# RoverBreakout2.net
KiCad netlist of a schematic drawn in Altium Designer
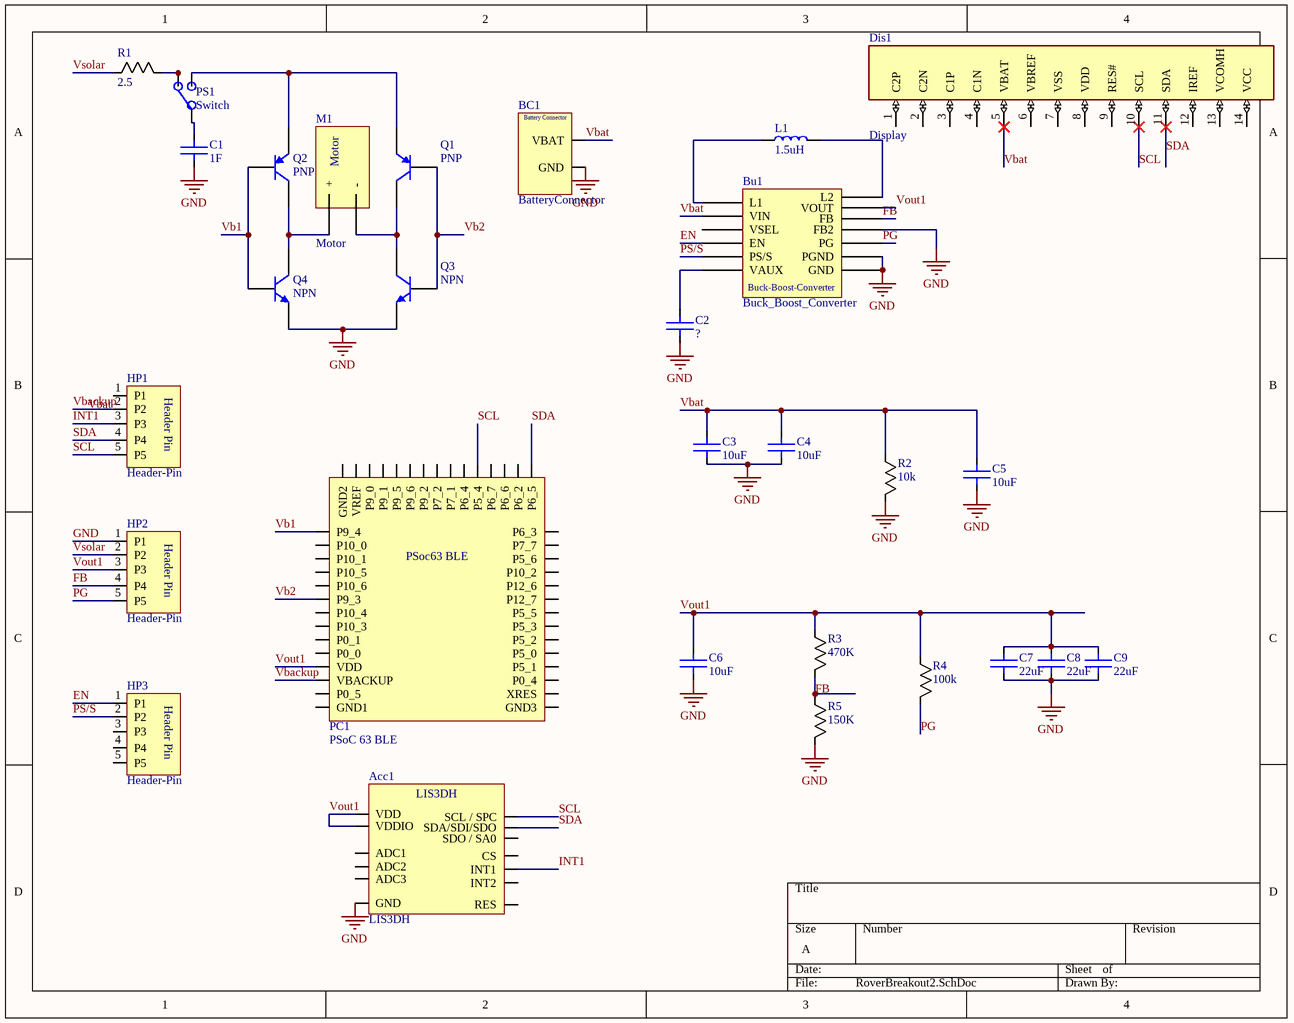
[diagram p0: RoverBreakout2.SchDoc]

(export (version "E")
  (design (tool "Eeschema 10.0.6"))
  (components
    (comp (ref "Acc1") (value "LIS3DH") (footprint "LIS3DH") (libsource (lib "SeniorDesign") (part "LIS3DH")))
    (comp (ref "BC1")
      (value "BatteryConnector")
      (footprint "BatteryConnector")
      (libsource (lib "SeniorDesign") (part "BatteryConnector"))
    )
    (comp (ref "Bu1")
      (value "Buck_Boost_Converter")
      (footprint "Buck_Boost_Converter")
      (libsource (lib "ISeniorDesign") (part "Buck_Boost_Converter"))
    )
    (comp (ref "C1")
      (value "1F")
      (footprint "PASSIVE-CAPACITOR-0603")
      (fields (field (name "Comment") "Capacitor1"))
      (libsource (lib "ISeniorDesign") (part "Capacitor1"))
    )
    (comp (ref "C2")
      (value "?")
      (footprint "PASSIVE-CAPACITOR-0603")
      (fields (field (name "Comment") "Capacitor1"))
      (libsource (lib "ISeniorDesign") (part "Capacitor1"))
    )
    (comp (ref "C3")
      (value "10uF")
      (footprint "PASSIVE-CAPACITOR-0603")
      (fields (field (name "Comment") "Capacitor1"))
      (libsource (lib "ISeniorDesign") (part "Capacitor1"))
    )
    (comp (ref "C4")
      (value "10uF")
      (footprint "PASSIVE-CAPACITOR-0603")
      (fields (field (name "Comment") "Capacitor1"))
      (libsource (lib "ISeniorDesign") (part "Capacitor1"))
    )
    (comp (ref "C5")
      (value "10uF")
      (footprint "PASSIVE-CAPACITOR-0603")
      (fields (field (name "Comment") "Capacitor1"))
      (libsource (lib "ISeniorDesign") (part "Capacitor1"))
    )
    (comp (ref "C6")
      (value "10uF")
      (footprint "PASSIVE-CAPACITOR-0603")
      (fields (field (name "Comment") "Capacitor1"))
      (libsource (lib "ISeniorDesign") (part "Capacitor1"))
    )
    (comp (ref "C7")
      (value "22uF")
      (footprint "PASSIVE-CAPACITOR-0603")
      (fields (field (name "Comment") "Capacitor1"))
      (libsource (lib "ISeniorDesign") (part "Capacitor1"))
    )
    (comp (ref "C8")
      (value "22uF")
      (footprint "PASSIVE-CAPACITOR-0603")
      (fields (field (name "Comment") "Capacitor1"))
      (libsource (lib "ISeniorDesign") (part "Capacitor1"))
    )
    (comp (ref "C9")
      (value "22uF")
      (footprint "PASSIVE-CAPACITOR-0603")
      (fields (field (name "Comment") "Capacitor1"))
      (libsource (lib "ISeniorDesign") (part "Capacitor1"))
    )
    (comp (ref "Dis1")
      (value "Display")
      (footprint "Display")
      (libsource (lib "SeniorDesign") (part "Display"))
    )
    (comp (ref "HP1")
      (value "Header-Pin")
      (footprint "Header_Pin")
      (libsource (lib "SeniorDesign") (part "Header-Pin"))
    )
    (comp (ref "HP2")
      (value "Header-Pin")
      (footprint "Header_Pin")
      (libsource (lib "SeniorDesign") (part "Header-Pin"))
    )
    (comp (ref "HP3")
      (value "Header-Pin")
      (footprint "Header_Pin")
      (libsource (lib "SeniorDesign") (part "Header-Pin"))
    )
    (comp (ref "L1")
      (value "1.5uH")
      (footprint "PASSIVE-INDUCTOR-0603")
      (fields (field (name "Comment") "Inductor"))
      (libsource (lib "ISeniorDesign") (part "Inductor"))
    )
    (comp (ref "M1") (value "Motor") (footprint "Motor") (libsource (lib "ISeniorDesign") (part "Motor")))
    (comp (ref "PC1")
      (value "PSoC 63 BLE")
      (footprint "PSoC-63 BLE")
      (libsource (lib "ISeniorDesign") (part "PSoC 63 BLE"))
    )
    (comp (ref "PS1")
      (value "Switch")
      (footprint "3-Way Switch")
      (libsource (lib "SeniorDesign") (part "Switch"))
    )
    (comp (ref "Q1")
      (value "PNP")
      (footprint "SOT-23B_N")
      (description "PNP Bipolar Transistor")
      (fields (field (name "PUBLISHER") "Altium Limited"))
      (libsource (lib "Miscellaneous Devices") (part "PNP"))
    )
    (comp (ref "Q2")
      (value "PNP")
      (footprint "SOT-23B_N")
      (description "PNP Bipolar Transistor")
      (fields (field (name "PUBLISHER") "Altium Limited"))
      (libsource (lib "Miscellaneous Devices") (part "PNP"))
    )
    (comp (ref "Q3")
      (value "NPN")
      (footprint "TO-226-AA")
      (description "NPN Bipolar Transistor")
      (fields (field (name "PUBLISHER") "Altium Limited"))
      (libsource (lib "Miscellaneous Devices") (part "NPN"))
    )
    (comp (ref "Q4")
      (value "NPN")
      (footprint "TO-226-AA")
      (description "NPN Bipolar Transistor")
      (fields (field (name "PUBLISHER") "Altium Limited"))
      (libsource (lib "Miscellaneous Devices") (part "NPN"))
    )
    (comp (ref "R1")
      (value "2.5")
      (footprint "PASSIVE-RESISTOR-0603")
      (fields (field (name "Comment") "Resistor"))
      (libsource (lib "ISeniorDesign") (part "Resistor1"))
    )
    (comp (ref "R2")
      (value "10k")
      (footprint "PASSIVE-RESISTOR-0603")
      (fields (field (name "Comment") "Resistor"))
      (libsource (lib "ISeniorDesign") (part "Resistor1"))
    )
    (comp (ref "R3")
      (value "470K")
      (footprint "PASSIVE-RESISTOR-0603")
      (fields (field (name "Comment") "Resistor"))
      (libsource (lib "ISeniorDesign") (part "Resistor1"))
    )
    (comp (ref "R4")
      (value "100k")
      (footprint "PASSIVE-RESISTOR-0603")
      (fields (field (name "Comment") "Resistor"))
      (libsource (lib "ISeniorDesign") (part "Resistor1"))
    )
    (comp (ref "R5")
      (value "150K")
      (footprint "PASSIVE-RESISTOR-0603")
      (fields (field (name "Comment") "Resistor"))
      (libsource (lib "ISeniorDesign") (part "Resistor1"))
    )
  )
  (nets
    (net (code "1") (name "/EN") (class "Default")
      (node (ref "Bu1") (pin "EN") (pinfunction "EN_EN") (pintype "passive"))
      (node (ref "HP3") (pin "1") (pinfunction "P1_1") (pintype "passive"))
    )
    (net (code "2") (name "/FB") (class "Default")
      (node (ref "Bu1") (pin "FB") (pinfunction "FB_FB") (pintype "passive"))
      (node (ref "HP2") (pin "4") (pinfunction "P4_4") (pintype "passive"))
      (node (ref "R3") (pin "2") (pinfunction "2_2") (pintype "passive"))
      (node (ref "R5") (pin "1") (pinfunction "1_1") (pintype "passive"))
    )
    (net (code "3") (name "/INT1") (class "Default")
      (node (ref "Acc1") (pin "INT1") (pinfunction "INT1_INT1") (pintype "passive"))
      (node (ref "HP1") (pin "3") (pinfunction "P3_3") (pintype "passive"))
    )
    (net (code "4") (name "/PG") (class "Default")
      (node (ref "Bu1") (pin "PG") (pinfunction "PG_PG") (pintype "passive"))
      (node (ref "HP2") (pin "5") (pinfunction "P5_5") (pintype "passive"))
      (node (ref "R4") (pin "2") (pinfunction "2_2") (pintype "passive"))
    )
    (net (code "5") (name "/PS{slash}S") (class "Default")
      (node (ref "Bu1") (pin "PS/S") (pinfunction "PS/S_PS/S") (pintype "passive"))
      (node (ref "HP3") (pin "2") (pinfunction "P2_2") (pintype "passive"))
    )
    (net (code "6") (name "/SCL") (class "Default")
      (node (ref "Acc1") (pin "SCL_/_SPC") (pinfunction "SCL_/_SPC_SCL_/_SPC") (pintype "passive"))
      (node (ref "Dis1") (pin "10") (pinfunction "SCL_10") (pintype "bidirectional"))
      (node (ref "HP1") (pin "5") (pinfunction "P5_5") (pintype "passive"))
      (node (ref "PC1") (pin "25") (pinfunction "P5_4_25") (pintype "passive"))
    )
    (net (code "7") (name "/SDA") (class "Default")
      (node (ref "Acc1") (pin "SDA/SDI/SDO") (pinfunction "SDA/SDI/SDO_SDA/SDI/SDO") (pintype "passive"))
      (node (ref "Dis1") (pin "11") (pinfunction "SDA_11") (pintype "bidirectional"))
      (node (ref "HP1") (pin "4") (pinfunction "P4_4") (pintype "passive"))
      (node (ref "PC1") (pin "29") (pinfunction "P6_5_29") (pintype "passive"))
    )
    (net (code "8") (name "/Vb1") (class "Default")
      (node (ref "PC1") (pin "14") (pinfunction "P9_4_14") (pintype "passive"))
      (node (ref "Q2") (pin "2") (pinfunction "B_2") (pintype "passive"))
      (node (ref "Q4") (pin "2") (pinfunction "B_2") (pintype "passive"))
    )
    (net (code "9") (name "/Vb2") (class "Default")
      (node (ref "PC1") (pin "9") (pinfunction "P9_3_9") (pintype "passive"))
      (node (ref "Q1") (pin "2") (pinfunction "B_2") (pintype "passive"))
      (node (ref "Q3") (pin "2") (pinfunction "B_2") (pintype "passive"))
    )
    (net (code "10") (name "/Vbackup") (class "Default")
      (node (ref "HP1") (pin "2") (pinfunction "P2_2") (pintype "passive"))
      (node (ref "PC1") (pin "3") (pinfunction "VBACKUP_3") (pintype "passive"))
    )
    (net (code "11") (name "/Vbat") (class "Default")
      (node (ref "BC1") (pin "VBAT") (pinfunction "VBAT_VBAT") (pintype "passive"))
      (node (ref "Bu1") (pin "VIN") (pinfunction "VIN_VIN") (pintype "passive"))
      (node (ref "C3") (pin "2") (pinfunction "2_2") (pintype "passive"))
      (node (ref "C4") (pin "2") (pinfunction "2_2") (pintype "passive"))
      (node (ref "C5") (pin "2") (pinfunction "2_2") (pintype "passive"))
      (node (ref "Dis1") (pin "5") (pinfunction "VBAT_5") (pintype "bidirectional"))
      (node (ref "HP1") (pin "1") (pinfunction "P1_1") (pintype "passive"))
      (node (ref "R2") (pin "1") (pinfunction "1_1") (pintype "passive"))
    )
    (net (code "12") (name "/Vout1") (class "Default")
      (node (ref "Acc1") (pin "VDD") (pinfunction "VDD_VDD") (pintype "passive"))
      (node (ref "Acc1") (pin "VDDIO") (pinfunction "VDDIO_VDDIO") (pintype "passive"))
      (node (ref "Bu1") (pin "VOUT") (pinfunction "VOUT_VOUT") (pintype "passive"))
      (node (ref "C6") (pin "2") (pinfunction "2_2") (pintype "passive"))
      (node (ref "C7") (pin "2") (pinfunction "2_2") (pintype "passive"))
      (node (ref "C8") (pin "2") (pinfunction "2_2") (pintype "passive"))
      (node (ref "C9") (pin "2") (pinfunction "2_2") (pintype "passive"))
      (node (ref "HP2") (pin "3") (pinfunction "P3_3") (pintype "passive"))
      (node (ref "PC1") (pin "4") (pinfunction "VDD_4") (pintype "passive"))
      (node (ref "R3") (pin "1") (pinfunction "1_1") (pintype "passive"))
      (node (ref "R4") (pin "1") (pinfunction "1_1") (pintype "passive"))
    )
    (net (code "13") (name "/Vsolar") (class "Default")
      (node (ref "HP2") (pin "2") (pinfunction "P2_2") (pintype "passive"))
      (node (ref "R1") (pin "1") (pinfunction "1_1") (pintype "passive"))
    )
    (net (code "14") (name "GND") (class "Default")
      (node (ref "Acc1") (pin "GND") (pinfunction "GND_GND") (pintype "passive"))
      (node (ref "BC1") (pin "GND") (pinfunction "GND_GND") (pintype "passive"))
      (node (ref "Bu1") (pin "FB2") (pinfunction "FB2_FB2") (pintype "passive"))
      (node (ref "Bu1") (pin "GND") (pinfunction "GND_GND") (pintype "passive"))
      (node (ref "Bu1") (pin "PGND") (pinfunction "PGND_PGND") (pintype "passive"))
      (node (ref "C1") (pin "1") (pinfunction "1_1") (pintype "passive"))
      (node (ref "C2") (pin "1") (pinfunction "1_1") (pintype "passive"))
      (node (ref "C3") (pin "1") (pinfunction "1_1") (pintype "passive"))
      (node (ref "C4") (pin "1") (pinfunction "1_1") (pintype "passive"))
      (node (ref "C5") (pin "1") (pinfunction "1_1") (pintype "passive"))
      (node (ref "C6") (pin "1") (pinfunction "1_1") (pintype "passive"))
      (node (ref "C7") (pin "1") (pinfunction "1_1") (pintype "passive"))
      (node (ref "C8") (pin "1") (pinfunction "1_1") (pintype "passive"))
      (node (ref "C9") (pin "1") (pinfunction "1_1") (pintype "passive"))
      (node (ref "HP2") (pin "1") (pinfunction "P1_1") (pintype "passive"))
      (node (ref "Q3") (pin "3") (pinfunction "E_3") (pintype "passive"))
      (node (ref "Q4") (pin "3") (pinfunction "E_3") (pintype "passive"))
      (node (ref "R2") (pin "2") (pinfunction "2_2") (pintype "passive"))
      (node (ref "R5") (pin "2") (pinfunction "2_2") (pintype "passive"))
    )
    (net (code "15") (name "Net-(Bu1-PadL1)") (class "Default")
      (node (ref "Bu1") (pin "L1") (pinfunction "L1_L1") (pintype "passive"))
      (node (ref "L1") (pin "1") (pinfunction "1_1") (pintype "passive"))
    )
    (net (code "16") (name "Net-(Bu1-PadL2)") (class "Default")
      (node (ref "Bu1") (pin "L2") (pinfunction "L2_L2") (pintype "passive"))
      (node (ref "L1") (pin "2") (pinfunction "2_2") (pintype "passive"))
    )
    (net (code "17") (name "Net-(Bu1-PadVAUX)") (class "Default")
      (node (ref "Bu1") (pin "VAUX") (pinfunction "VAUX_VAUX") (pintype "passive"))
      (node (ref "C2") (pin "2") (pinfunction "2_2") (pintype "passive"))
    )
    (net (code "18") (name "Net-(C1-Pad2)") (class "Default")
      (node (ref "C1") (pin "2") (pinfunction "2_2") (pintype "passive"))
      (node (ref "PS1") (pin "2") (pinfunction "2_2") (pintype "passive"))
    )
    (net (code "19") (name "Net-(M1-+)") (class "Default")
      (node (ref "M1") (pin "1") (pinfunction "+_1") (pintype "passive"))
      (node (ref "Q2") (pin "1") (pinfunction "C_1") (pintype "passive"))
      (node (ref "Q4") (pin "1") (pinfunction "C_1") (pintype "passive"))
    )
    (net (code "20") (name "Net-(M1--)") (class "Default")
      (node (ref "M1") (pin "2") (pinfunction "-_2") (pintype "passive"))
      (node (ref "Q1") (pin "1") (pinfunction "C_1") (pintype "passive"))
      (node (ref "Q3") (pin "1") (pinfunction "C_1") (pintype "passive"))
    )
    (net (code "21") (name "Net-(PS1-Pad1)") (class "Default")
      (node (ref "PS1") (pin "1") (pinfunction "1_1") (pintype "passive"))
      (node (ref "R1") (pin "2") (pinfunction "2_2") (pintype "passive"))
    )
    (net (code "22") (name "Net-(Q1-E)") (class "Default")
      (node (ref "PS1") (pin "3") (pinfunction "3_3") (pintype "passive"))
      (node (ref "Q1") (pin "3") (pinfunction "E_3") (pintype "passive"))
      (node (ref "Q2") (pin "3") (pinfunction "E_3") (pintype "passive"))
    )
    (net (code "23") (name "unconnected-(Acc1-PadADC1)") (class "Default")
      (node (ref "Acc1") (pin "ADC1") (pinfunction "ADC1_ADC1") (pintype "passive"))
    )
    (net (code "24") (name "unconnected-(Acc1-PadADC2)") (class "Default")
      (node (ref "Acc1") (pin "ADC2") (pinfunction "ADC2_ADC2") (pintype "passive"))
    )
    (net (code "25") (name "unconnected-(Acc1-PadADC3)") (class "Default")
      (node (ref "Acc1") (pin "ADC3") (pinfunction "ADC3_ADC3") (pintype "passive"))
    )
    (net (code "26") (name "unconnected-(Acc1-PadCS)") (class "Default")
      (node (ref "Acc1") (pin "CS") (pinfunction "CS_CS") (pintype "passive"))
    )
    (net (code "27") (name "unconnected-(Acc1-PadINT2)") (class "Default")
      (node (ref "Acc1") (pin "INT2") (pinfunction "INT2_INT2") (pintype "passive"))
    )
    (net (code "28") (name "unconnected-(Acc1-PadRES)") (class "Default")
      (node (ref "Acc1") (pin "RES") (pinfunction "RES_RES") (pintype "passive"))
    )
    (net (code "29") (name "unconnected-(Acc1-PadSDO_{slash}_SA0)") (class "Default")
      (node (ref "Acc1") (pin "SDO_/_SA0") (pinfunction "SDO_/_SA0_SDO_/_SA0") (pintype "passive"))
    )
    (net (code "30") (name "unconnected-(Bu1-PadVSEL)") (class "Default")
      (node (ref "Bu1") (pin "VSEL") (pinfunction "VSEL_VSEL") (pintype "passive"))
    )
    (net (code "31") (name "unconnected-(Dis1-C1N-Pad4)") (class "Default")
      (node (ref "Dis1") (pin "4") (pinfunction "C1N_4") (pintype "bidirectional"))
    )
    (net (code "32") (name "unconnected-(Dis1-C1P-Pad3)") (class "Default")
      (node (ref "Dis1") (pin "3") (pinfunction "C1P_3") (pintype "bidirectional"))
    )
    (net (code "33") (name "unconnected-(Dis1-C2N-Pad2)") (class "Default")
      (node (ref "Dis1") (pin "2") (pinfunction "C2N_2") (pintype "bidirectional"))
    )
    (net (code "34") (name "unconnected-(Dis1-C2P-Pad1)") (class "Default")
      (node (ref "Dis1") (pin "1") (pinfunction "C2P_1") (pintype "bidirectional"))
    )
    (net (code "35") (name "unconnected-(Dis1-IREF-Pad12)") (class "Default")
      (node (ref "Dis1") (pin "12") (pinfunction "IREF_12") (pintype "bidirectional"))
    )
    (net (code "36") (name "unconnected-(Dis1-RES#-Pad9)") (class "Default")
      (node (ref "Dis1") (pin "9") (pinfunction "RES#_9") (pintype "bidirectional"))
    )
    (net (code "37") (name "unconnected-(Dis1-VBREF-Pad6)") (class "Default")
      (node (ref "Dis1") (pin "6") (pinfunction "VBREF_6") (pintype "bidirectional"))
    )
    (net (code "38") (name "unconnected-(Dis1-VCC-Pad14)") (class "Default")
      (node (ref "Dis1") (pin "14") (pinfunction "VCC_14") (pintype "bidirectional"))
    )
    (net (code "39") (name "unconnected-(Dis1-VCOMH-Pad13)") (class "Default")
      (node (ref "Dis1") (pin "13") (pinfunction "VCOMH_13") (pintype "bidirectional"))
    )
    (net (code "40") (name "unconnected-(Dis1-VDD-Pad8)") (class "Default")
      (node (ref "Dis1") (pin "8") (pinfunction "VDD_8") (pintype "bidirectional"))
    )
    (net (code "41") (name "unconnected-(Dis1-VSS-Pad7)") (class "Default")
      (node (ref "Dis1") (pin "7") (pinfunction "VSS_7") (pintype "bidirectional"))
    )
    (net (code "42") (name "unconnected-(HP3-P3-Pad3)") (class "Default")
      (node (ref "HP3") (pin "3") (pinfunction "P3_3") (pintype "passive"))
    )
    (net (code "43") (name "unconnected-(HP3-P4-Pad4)") (class "Default")
      (node (ref "HP3") (pin "4") (pinfunction "P4_4") (pintype "passive"))
    )
    (net (code "44") (name "unconnected-(HP3-P5-Pad5)") (class "Default")
      (node (ref "HP3") (pin "5") (pinfunction "P5_5") (pintype "passive"))
    )
    (net (code "45") (name "unconnected-(PC1-GND1-Pad1)") (class "Default")
      (node (ref "PC1") (pin "1") (pinfunction "GND1_1") (pintype "passive"))
    )
    (net (code "46") (name "unconnected-(PC1-GND2-Pad15)") (class "Default")
      (node (ref "PC1") (pin "15") (pinfunction "GND2_15") (pintype "passive"))
    )
    (net (code "47") (name "unconnected-(PC1-GND3-Pad43)") (class "Default")
      (node (ref "PC1") (pin "43") (pinfunction "GND3_43") (pintype "passive"))
    )
    (net (code "48") (name "unconnected-(PC1-P0_0-Pad5)") (class "Default")
      (node (ref "PC1") (pin "5") (pinfunction "P0_0_5") (pintype "passive"))
    )
    (net (code "49") (name "unconnected-(PC1-P0_1-Pad6)") (class "Default")
      (node (ref "PC1") (pin "6") (pinfunction "P0_1_6") (pintype "passive"))
    )
    (net (code "50") (name "unconnected-(PC1-P0_4-Pad41)") (class "Default")
      (node (ref "PC1") (pin "41") (pinfunction "P0_4_41") (pintype "passive"))
    )
    (net (code "51") (name "unconnected-(PC1-P0_5-Pad2)") (class "Default")
      (node (ref "PC1") (pin "2") (pinfunction "P0_5_2") (pintype "passive"))
    )
    (net (code "52") (name "unconnected-(PC1-P5_0-Pad39)") (class "Default")
      (node (ref "PC1") (pin "39") (pinfunction "P5_0_39") (pintype "passive"))
    )
    (net (code "53") (name "unconnected-(PC1-P5_1-Pad40)") (class "Default")
      (node (ref "PC1") (pin "40") (pinfunction "P5_1_40") (pintype "passive"))
    )
    (net (code "54") (name "unconnected-(PC1-P5_2-Pad38)") (class "Default")
      (node (ref "PC1") (pin "38") (pinfunction "P5_2_38") (pintype "passive"))
    )
    (net (code "55") (name "unconnected-(PC1-P5_3-Pad37)") (class "Default")
      (node (ref "PC1") (pin "37") (pinfunction "P5_3_37") (pintype "passive"))
    )
    (net (code "56") (name "unconnected-(PC1-P5_5-Pad36)") (class "Default")
      (node (ref "PC1") (pin "36") (pinfunction "P5_5_36") (pintype "passive"))
    )
    (net (code "57") (name "unconnected-(PC1-P5_6-Pad32)") (class "Default")
      (node (ref "PC1") (pin "32") (pinfunction "P5_6_32") (pintype "passive"))
    )
    (net (code "58") (name "unconnected-(PC1-P6_2-Pad28)") (class "Default")
      (node (ref "PC1") (pin "28") (pinfunction "P6_2_28") (pintype "passive"))
    )
    (net (code "59") (name "unconnected-(PC1-P6_3-Pad30)") (class "Default")
      (node (ref "PC1") (pin "30") (pinfunction "P6_3_30") (pintype "passive"))
    )
    (net (code "60") (name "unconnected-(PC1-P6_4-Pad24)") (class "Default")
      (node (ref "PC1") (pin "24") (pinfunction "P6_4_24") (pintype "passive"))
    )
    (net (code "61") (name "unconnected-(PC1-P6_6-Pad27)") (class "Default")
      (node (ref "PC1") (pin "27") (pinfunction "P6_6_27") (pintype "passive"))
    )
    (net (code "62") (name "unconnected-(PC1-P6_7-Pad26)") (class "Default")
      (node (ref "PC1") (pin "26") (pinfunction "P6_7_26") (pintype "passive"))
    )
    (net (code "63") (name "unconnected-(PC1-P7_1-Pad23)") (class "Default")
      (node (ref "PC1") (pin "23") (pinfunction "P7_1_23") (pintype "passive"))
    )
    (net (code "64") (name "unconnected-(PC1-P7_2-Pad22)") (class "Default")
      (node (ref "PC1") (pin "22") (pinfunction "P7_2_22") (pintype "passive"))
    )
    (net (code "65") (name "unconnected-(PC1-P7_7-Pad31)") (class "Default")
      (node (ref "PC1") (pin "31") (pinfunction "P7_7_31") (pintype "passive"))
    )
    (net (code "66") (name "unconnected-(PC1-P9_0-Pad17)") (class "Default")
      (node (ref "PC1") (pin "17") (pinfunction "P9_0_17") (pintype "passive"))
    )
    (net (code "67") (name "unconnected-(PC1-P9_1-Pad18)") (class "Default")
      (node (ref "PC1") (pin "18") (pinfunction "P9_1_18") (pintype "passive"))
    )
    (net (code "68") (name "unconnected-(PC1-P9_2-Pad21)") (class "Default")
      (node (ref "PC1") (pin "21") (pinfunction "P9_2_21") (pintype "passive"))
    )
    (net (code "69") (name "unconnected-(PC1-P9_5-Pad19)") (class "Default")
      (node (ref "PC1") (pin "19") (pinfunction "P9_5_19") (pintype "passive"))
    )
    (net (code "70") (name "unconnected-(PC1-P9_6-Pad20)") (class "Default")
      (node (ref "PC1") (pin "20") (pinfunction "P9_6_20") (pintype "passive"))
    )
    (net (code "71") (name "unconnected-(PC1-P10_0-Pad13)") (class "Default")
      (node (ref "PC1") (pin "13") (pinfunction "P10_0_13") (pintype "passive"))
    )
    (net (code "72") (name "unconnected-(PC1-P10_1-Pad12)") (class "Default")
      (node (ref "PC1") (pin "12") (pinfunction "P10_1_12") (pintype "passive"))
    )
    (net (code "73") (name "unconnected-(PC1-P10_2-Pad33)") (class "Default")
      (node (ref "PC1") (pin "33") (pinfunction "P10_2_33") (pintype "passive"))
    )
    (net (code "74") (name "unconnected-(PC1-P10_3-Pad7)") (class "Default")
      (node (ref "PC1") (pin "7") (pinfunction "P10_3_7") (pintype "passive"))
    )
    (net (code "75") (name "unconnected-(PC1-P10_4-Pad8)") (class "Default")
      (node (ref "PC1") (pin "8") (pinfunction "P10_4_8") (pintype "passive"))
    )
    (net (code "76") (name "unconnected-(PC1-P10_5-Pad11)") (class "Default")
      (node (ref "PC1") (pin "11") (pinfunction "P10_5_11") (pintype "passive"))
    )
    (net (code "77") (name "unconnected-(PC1-P10_6-Pad10)") (class "Default")
      (node (ref "PC1") (pin "10") (pinfunction "P10_6_10") (pintype "passive"))
    )
    (net (code "78") (name "unconnected-(PC1-P12_6-Pad34)") (class "Default")
      (node (ref "PC1") (pin "34") (pinfunction "P12_6_34") (pintype "passive"))
    )
    (net (code "79") (name "unconnected-(PC1-P12_7-Pad35)") (class "Default")
      (node (ref "PC1") (pin "35") (pinfunction "P12_7_35") (pintype "passive"))
    )
    (net (code "80") (name "unconnected-(PC1-VREF-Pad16)") (class "Default")
      (node (ref "PC1") (pin "16") (pinfunction "VREF_16") (pintype "passive"))
    )
    (net (code "81") (name "unconnected-(PC1-XRES-Pad42)") (class "Default")
      (node (ref "PC1") (pin "42") (pinfunction "XRES_42") (pintype "passive"))
    )
  )
)
